# Core.net
KiCad netlist of a schematic drawn in Altium Designer
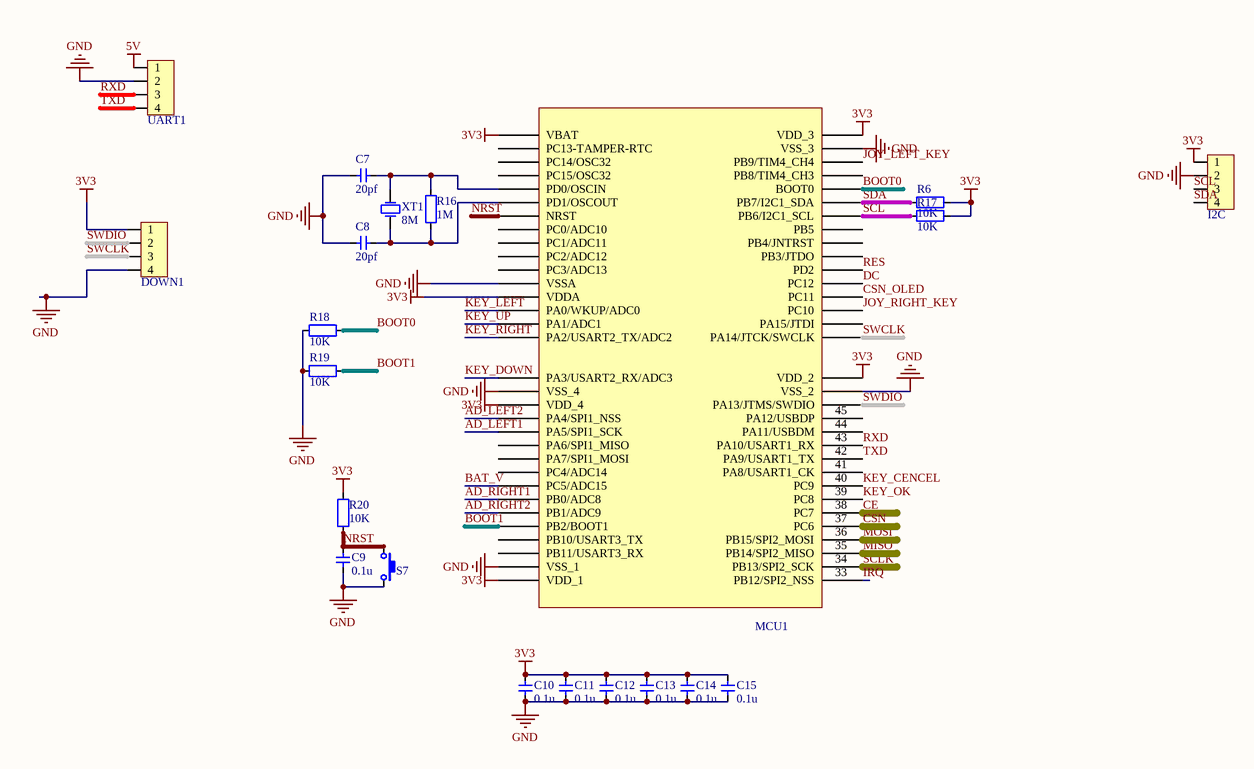
[diagram p0: Core.SchDoc]

(export (version "E")
  (design (tool "Eeschema 10.0.6"))
  (components
    (comp (ref "C7")
      (value "20pf")
      (footprint "PCB_PassiveCap:CAP_0603")
      (description "Capacitor")
      (fields (field (name "Comment") "Cap_0603"))
      (libsource (lib "SCH_Passive") (part "Cap_0603"))
    )
    (comp (ref "C8")
      (value "20pf")
      (footprint "PCB_PassiveCap:CAP_0603")
      (description "Capacitor")
      (fields (field (name "Comment") "Cap_0603"))
      (libsource (lib "SCH_Passive") (part "Cap_0603"))
    )
    (comp (ref "C9")
      (value "0.1u")
      (footprint "PCB_PassiveCap:CAP_0603")
      (description "Capacitor")
      (fields (field (name "Comment") "Cap_0603"))
      (libsource (lib "SCH_Passive") (part "Cap_0603"))
    )
    (comp (ref "C10")
      (value "0.1u")
      (footprint "PCB_PassiveCap:CAP_0603")
      (description "Capacitor")
      (fields (field (name "Comment") "Cap_0603"))
      (libsource (lib "SCH_Passive") (part "Cap_0603"))
    )
    (comp (ref "C11")
      (value "0.1u")
      (footprint "PCB_PassiveCap:CAP_0603")
      (description "Capacitor")
      (fields (field (name "Comment") "Cap_0603"))
      (libsource (lib "SCH_Passive") (part "Cap_0603"))
    )
    (comp (ref "C12")
      (value "0.1u")
      (footprint "PCB_PassiveCap:CAP_0603")
      (description "Capacitor")
      (fields (field (name "Comment") "Cap_0603"))
      (libsource (lib "SCH_Passive") (part "Cap_0603"))
    )
    (comp (ref "C13")
      (value "0.1u")
      (footprint "PCB_PassiveCap:CAP_0603")
      (description "Capacitor")
      (fields (field (name "Comment") "Cap_0603"))
      (libsource (lib "SCH_Passive") (part "Cap_0603"))
    )
    (comp (ref "C14")
      (value "0.1u")
      (footprint "PCB_PassiveCap:CAP_0603")
      (description "Capacitor")
      (fields (field (name "Comment") "Cap_0603"))
      (libsource (lib "SCH_Passive") (part "Cap_0603"))
    )
    (comp (ref "C15")
      (value "0.1u")
      (footprint "PCB_PassiveCap:CAP_0603")
      (description "Capacitor")
      (fields (field (name "Comment") "Cap_0603"))
      (libsource (lib "SCH_Passive") (part "Cap_0603"))
    )
    (comp (ref "DOWN1")
      (value "HDR1x4_2.54")
      (footprint "PCB_ConnectorHDR:HDR1x4_2.54_180")
      (description "Header")
      (libsource (lib "SCH_ConnectorHDR") (part "HDR1x4_2.54"))
    )
    (comp (ref "I2C")
      (value "HDR1x4_2.54")
      (footprint "PCB_ConnectorHDR:HDR1x4_2.54_180")
      (description "Header")
      (libsource (lib "SCH_ConnectorHDR") (part "HDR1x4_2.54"))
    )
    (comp (ref "MCU1")
      (value "STM32F103RC")
      (footprint "LQFP_P0.5_64")
      (description "MCU")
      (libsource (lib "SCH_IntegratedCircuit") (part "STM32F103RC"))
    )
    (comp (ref "R6")
      (value "10K")
      (footprint "PCB_PassiveRes:RES_0603")
      (description "Resistor")
      (fields (field (name "Comment") "Res_0603"))
      (libsource (lib "") (part "Res_0603_2"))
    )
    (comp (ref "R16")
      (value "1M")
      (footprint "PCB_PassiveRes:RES_0603")
      (description "Resistor")
      (fields (field (name "Comment") "Res_0603"))
      (libsource (lib "") (part "Res_0603_1"))
    )
    (comp (ref "R17")
      (value "10K")
      (footprint "PCB_PassiveRes:RES_0603")
      (description "Resistor")
      (fields (field (name "Comment") "Res_0603"))
      (libsource (lib "") (part "Res_0603_2"))
    )
    (comp (ref "R18")
      (value "10K")
      (footprint "PCB_PassiveRes:RES_0603")
      (description "Resistor")
      (fields (field (name "Comment") "Res_0603"))
      (libsource (lib "SCH_Passive") (part "Res_0603"))
    )
    (comp (ref "R19")
      (value "10K")
      (footprint "PCB_PassiveRes:RES_0603")
      (description "Resistor")
      (fields (field (name "Comment") "Res_0603"))
      (libsource (lib "SCH_Passive") (part "Res_0603"))
    )
    (comp (ref "R20")
      (value "10K")
      (footprint "PCB_PassiveRes:RES_0603")
      (description "Resistor")
      (fields (field (name "Comment") "Res_0603"))
      (libsource (lib "") (part "Res_0603_3"))
    )
    (comp (ref "S7")
      (value "ButtonTACT_3x4x2_180")
      (footprint "PCB_Switch:ButtonTACT_3x4x2_180H")
      (description "Button")
      (libsource (lib "SCH_Switch") (part "ButtonTACT_3x4x2_180"))
    )
    (comp (ref "UART1")
      (value "HDR1x4_2.54")
      (footprint "PCB_ConnectorHDR:HDR1x4_2.54_180")
      (description "Header")
      (libsource (lib "SCH_ConnectorHDR") (part "HDR1x4_2.54"))
    )
    (comp (ref "XT1")
      (value "8M")
      (footprint "PCB_Oscillator:XT_5032_2")
      (description "Crystal Oscillator")
      (fields (field (name "Comment") "XTAL_5032_2P"))
      (libsource (lib "SCH_Oscillator") (part "XTAL_5032_2P"))
    )
  )
  (nets
    (net (code "1") (name "/AD_LEFT1") (class "Default")
      (node (ref "MCU1") (pin "21") (pinfunction "PA5/SPI1_SCK_21") (pintype "passive"))
    )
    (net (code "2") (name "/AD_LEFT2") (class "Default")
      (node (ref "MCU1") (pin "20") (pinfunction "PA4/SPI1_NSS_20") (pintype "passive"))
    )
    (net (code "3") (name "/AD_RIGHT1") (class "Default")
      (node (ref "MCU1") (pin "26") (pinfunction "PB0/ADC8_26") (pintype "passive"))
    )
    (net (code "4") (name "/AD_RIGHT2") (class "Default")
      (node (ref "MCU1") (pin "27") (pinfunction "PB1/ADC9_27") (pintype "passive"))
    )
    (net (code "5") (name "/BAT_V") (class "Default")
      (node (ref "MCU1") (pin "25") (pinfunction "PC5/ADC15_25") (pintype "passive"))
    )
    (net (code "6") (name "/BOOT0") (class "Default")
      (node (ref "MCU1") (pin "60") (pinfunction "BOOT0_60") (pintype "passive"))
      (node (ref "R18") (pin "1") (pinfunction "1_1") (pintype "passive"))
    )
    (net (code "7") (name "/BOOT1") (class "Default")
      (node (ref "MCU1") (pin "28") (pinfunction "PB2/BOOT1_28") (pintype "passive"))
      (node (ref "R19") (pin "1") (pinfunction "1_1") (pintype "passive"))
    )
    (net (code "8") (name "/CE") (class "Default")
      (node (ref "MCU1") (pin "38") (pinfunction "PC7_38") (pintype "passive"))
    )
    (net (code "9") (name "/CSN") (class "Default")
      (node (ref "MCU1") (pin "37") (pinfunction "PC6_37") (pintype "passive"))
    )
    (net (code "10") (name "/CSN_OLED") (class "Default")
      (node (ref "MCU1") (pin "52") (pinfunction "PC11_52") (pintype "passive"))
    )
    (net (code "11") (name "/DC") (class "Default")
      (node (ref "MCU1") (pin "53") (pinfunction "PC12_53") (pintype "passive"))
    )
    (net (code "12") (name "/IRQ") (class "Default")
      (node (ref "MCU1") (pin "33") (pinfunction "PB12/SPI2_NSS_33") (pintype "passive"))
    )
    (net (code "13") (name "/JOY_LEFT_KEY") (class "Default")
      (node (ref "MCU1") (pin "62") (pinfunction "PB9/TIM4_CH4_62") (pintype "passive"))
    )
    (net (code "14") (name "/JOY_RIGHT_KEY") (class "Default")
      (node (ref "MCU1") (pin "51") (pinfunction "PC10_51") (pintype "passive"))
    )
    (net (code "15") (name "/KEY_CENCEL") (class "Default")
      (node (ref "MCU1") (pin "40") (pinfunction "PC9_40") (pintype "passive"))
    )
    (net (code "16") (name "/KEY_DOWN") (class "Default")
      (node (ref "MCU1") (pin "17") (pinfunction "PA3/USART2_RX/ADC3_17") (pintype "passive"))
    )
    (net (code "17") (name "/KEY_LEFT") (class "Default")
      (node (ref "MCU1") (pin "14") (pinfunction "PA0/WKUP/ADC0_14") (pintype "passive"))
    )
    (net (code "18") (name "/KEY_OK") (class "Default")
      (node (ref "MCU1") (pin "39") (pinfunction "PC8_39") (pintype "passive"))
    )
    (net (code "19") (name "/KEY_RIGHT") (class "Default")
      (node (ref "MCU1") (pin "16") (pinfunction "PA2/USART2_TX/ADC2_16") (pintype "passive"))
    )
    (net (code "20") (name "/KEY_UP") (class "Default")
      (node (ref "MCU1") (pin "15") (pinfunction "PA1/ADC1_15") (pintype "passive"))
    )
    (net (code "21") (name "/MISO") (class "Default")
      (node (ref "MCU1") (pin "35") (pinfunction "PB14/SPI2_MISO_35") (pintype "passive"))
    )
    (net (code "22") (name "/MOSI") (class "Default")
      (node (ref "MCU1") (pin "36") (pinfunction "PB15/SPI2_MOSI_36") (pintype "passive"))
    )
    (net (code "23") (name "/NRST") (class "Default")
      (node (ref "C9") (pin "2") (pinfunction "2_2") (pintype "passive"))
      (node (ref "MCU1") (pin "7") (pinfunction "NRST_7") (pintype "passive"))
      (node (ref "R20") (pin "2") (pinfunction "2_2") (pintype "passive"))
      (node (ref "S7") (pin "1") (pinfunction "1_1") (pintype "passive"))
    )
    (net (code "24") (name "/RES") (class "Default")
      (node (ref "MCU1") (pin "54") (pinfunction "PD2_54") (pintype "passive"))
    )
    (net (code "25") (name "/RXD") (class "Default")
      (node (ref "MCU1") (pin "43") (pinfunction "PA10/USART1_RX_43") (pintype "passive"))
      (node (ref "UART1") (pin "3") (pinfunction "3_3") (pintype "passive"))
    )
    (net (code "26") (name "/SCL") (class "Default")
      (node (ref "I2C") (pin "3") (pinfunction "3_3") (pintype "passive"))
      (node (ref "MCU1") (pin "58") (pinfunction "PB6/I2C1_SCL_58") (pintype "passive"))
      (node (ref "R17") (pin "1") (pinfunction "1_1") (pintype "passive"))
    )
    (net (code "27") (name "/SCLK") (class "Default")
      (node (ref "MCU1") (pin "34") (pinfunction "PB13/SPI2_SCK_34") (pintype "passive"))
    )
    (net (code "28") (name "/SDA") (class "Default")
      (node (ref "I2C") (pin "4") (pinfunction "4_4") (pintype "passive"))
      (node (ref "MCU1") (pin "59") (pinfunction "PB7/I2C1_SDA_59") (pintype "passive"))
      (node (ref "R6") (pin "1") (pinfunction "1_1") (pintype "passive"))
    )
    (net (code "29") (name "/SWCLK") (class "Default")
      (node (ref "DOWN1") (pin "3") (pinfunction "3_3") (pintype "passive"))
      (node (ref "MCU1") (pin "49") (pinfunction "PA14/JTCK/SWCLK_49") (pintype "passive"))
    )
    (net (code "30") (name "/SWDIO") (class "Default")
      (node (ref "DOWN1") (pin "2") (pinfunction "2_2") (pintype "passive"))
      (node (ref "MCU1") (pin "46") (pinfunction "PA13/JTMS/SWDIO_46") (pintype "passive"))
    )
    (net (code "31") (name "/TXD") (class "Default")
      (node (ref "MCU1") (pin "42") (pinfunction "PA9/USART1_TX_42") (pintype "passive"))
      (node (ref "UART1") (pin "4") (pinfunction "4_4") (pintype "passive"))
    )
    (net (code "32") (name "3V3") (class "Default")
      (node (ref "C10") (pin "2") (pinfunction "2_2") (pintype "passive"))
      (node (ref "C11") (pin "2") (pinfunction "2_2") (pintype "passive"))
      (node (ref "C12") (pin "2") (pinfunction "2_2") (pintype "passive"))
      (node (ref "C13") (pin "2") (pinfunction "2_2") (pintype "passive"))
      (node (ref "C14") (pin "2") (pinfunction "2_2") (pintype "passive"))
      (node (ref "C15") (pin "2") (pinfunction "2_2") (pintype "passive"))
      (node (ref "DOWN1") (pin "1") (pinfunction "1_1") (pintype "passive"))
      (node (ref "I2C") (pin "1") (pinfunction "1_1") (pintype "passive"))
      (node (ref "MCU1") (pin "1") (pinfunction "VBAT_1") (pintype "passive"))
      (node (ref "MCU1") (pin "13") (pinfunction "VDDA_13") (pintype "passive"))
      (node (ref "MCU1") (pin "19") (pinfunction "VDD_4_19") (pintype "passive"))
      (node (ref "MCU1") (pin "32") (pinfunction "VDD_1_32") (pintype "passive"))
      (node (ref "MCU1") (pin "48") (pinfunction "VDD_2_48") (pintype "passive"))
      (node (ref "MCU1") (pin "64") (pinfunction "VDD_3_64") (pintype "passive"))
      (node (ref "R17") (pin "2") (pinfunction "2_2") (pintype "passive"))
      (node (ref "R20") (pin "1") (pinfunction "1_1") (pintype "passive"))
      (node (ref "R6") (pin "2") (pinfunction "2_2") (pintype "passive"))
    )
    (net (code "33") (name "5V") (class "Default")
      (node (ref "UART1") (pin "1") (pinfunction "1_1") (pintype "passive"))
    )
    (net (code "34") (name "GND") (class "Default")
      (node (ref "C10") (pin "1") (pinfunction "1_1") (pintype "passive"))
      (node (ref "C11") (pin "1") (pinfunction "1_1") (pintype "passive"))
      (node (ref "C12") (pin "1") (pinfunction "1_1") (pintype "passive"))
      (node (ref "C13") (pin "1") (pinfunction "1_1") (pintype "passive"))
      (node (ref "C14") (pin "1") (pinfunction "1_1") (pintype "passive"))
      (node (ref "C15") (pin "1") (pinfunction "1_1") (pintype "passive"))
      (node (ref "C7") (pin "1") (pinfunction "1_1") (pintype "passive"))
      (node (ref "C8") (pin "1") (pinfunction "1_1") (pintype "passive"))
      (node (ref "C9") (pin "1") (pinfunction "1_1") (pintype "passive"))
      (node (ref "DOWN1") (pin "4") (pinfunction "4_4") (pintype "passive"))
      (node (ref "I2C") (pin "2") (pinfunction "2_2") (pintype "passive"))
      (node (ref "MCU1") (pin "12") (pinfunction "VSSA_12") (pintype "passive"))
      (node (ref "MCU1") (pin "18") (pinfunction "VSS_4_18") (pintype "passive"))
      (node (ref "MCU1") (pin "31") (pinfunction "VSS_1_31") (pintype "passive"))
      (node (ref "MCU1") (pin "47") (pinfunction "VSS_2_47") (pintype "passive"))
      (node (ref "MCU1") (pin "63") (pinfunction "VSS_3_63") (pintype "passive"))
      (node (ref "R18") (pin "2") (pinfunction "2_2") (pintype "passive"))
      (node (ref "R19") (pin "2") (pinfunction "2_2") (pintype "passive"))
      (node (ref "S7") (pin "2") (pinfunction "2_2") (pintype "passive"))
      (node (ref "UART1") (pin "2") (pinfunction "2_2") (pintype "passive"))
    )
    (net (code "35") (name "Net-(MCU1-PD0{slash}OSCIN)") (class "Default")
      (node (ref "C7") (pin "2") (pinfunction "2_2") (pintype "passive"))
      (node (ref "MCU1") (pin "5") (pinfunction "PD0/OSCIN_5") (pintype "passive"))
      (node (ref "R16") (pin "2") (pinfunction "2_2") (pintype "passive"))
      (node (ref "XT1") (pin "2") (pinfunction "OSC2_2") (pintype "passive"))
    )
    (net (code "36") (name "Net-(MCU1-PD1{slash}OSCOUT)") (class "Default")
      (node (ref "C8") (pin "2") (pinfunction "2_2") (pintype "passive"))
      (node (ref "MCU1") (pin "6") (pinfunction "PD1/OSCOUT_6") (pintype "passive"))
      (node (ref "R16") (pin "1") (pinfunction "1_1") (pintype "passive"))
      (node (ref "XT1") (pin "1") (pinfunction "OSC1_1") (pintype "passive"))
    )
    (net (code "37") (name "unconnected-(MCU1-PA6{slash}SPI1_MISO-Pad22)") (class "Default")
      (node (ref "MCU1") (pin "22") (pinfunction "PA6/SPI1_MISO_22") (pintype "passive"))
    )
    (net (code "38") (name "unconnected-(MCU1-PA7{slash}SPI1_MOSI-Pad23)") (class "Default")
      (node (ref "MCU1") (pin "23") (pinfunction "PA7/SPI1_MOSI_23") (pintype "passive"))
    )
    (net (code "39") (name "unconnected-(MCU1-PA8{slash}USART1_CK-Pad41)") (class "Default")
      (node (ref "MCU1") (pin "41") (pinfunction "PA8/USART1_CK_41") (pintype "passive"))
    )
    (net (code "40") (name "unconnected-(MCU1-PA11{slash}USBDM-Pad44)") (class "Default")
      (node (ref "MCU1") (pin "44") (pinfunction "PA11/USBDM_44") (pintype "passive"))
    )
    (net (code "41") (name "unconnected-(MCU1-PA12{slash}USBDP-Pad45)") (class "Default")
      (node (ref "MCU1") (pin "45") (pinfunction "PA12/USBDP_45") (pintype "passive"))
    )
    (net (code "42") (name "unconnected-(MCU1-PA15{slash}JTDI-Pad50)") (class "Default")
      (node (ref "MCU1") (pin "50") (pinfunction "PA15/JTDI_50") (pintype "passive"))
    )
    (net (code "43") (name "unconnected-(MCU1-PB3{slash}JTDO-Pad55)") (class "Default")
      (node (ref "MCU1") (pin "55") (pinfunction "PB3/JTDO_55") (pintype "passive"))
    )
    (net (code "44") (name "unconnected-(MCU1-PB4{slash}JNTRST-Pad56)") (class "Default")
      (node (ref "MCU1") (pin "56") (pinfunction "PB4/JNTRST_56") (pintype "passive"))
    )
    (net (code "45") (name "unconnected-(MCU1-PB5-Pad57)") (class "Default")
      (node (ref "MCU1") (pin "57") (pinfunction "PB5_57") (pintype "passive"))
    )
    (net (code "46") (name "unconnected-(MCU1-PB8{slash}TIM4_CH3-Pad61)") (class "Default")
      (node (ref "MCU1") (pin "61") (pinfunction "PB8/TIM4_CH3_61") (pintype "passive"))
    )
    (net (code "47") (name "unconnected-(MCU1-PB10{slash}USART3_TX-Pad29)") (class "Default")
      (node (ref "MCU1") (pin "29") (pinfunction "PB10/USART3_TX_29") (pintype "passive"))
    )
    (net (code "48") (name "unconnected-(MCU1-PB11{slash}USART3_RX-Pad30)") (class "Default")
      (node (ref "MCU1") (pin "30") (pinfunction "PB11/USART3_RX_30") (pintype "passive"))
    )
    (net (code "49") (name "unconnected-(MCU1-PC0{slash}ADC10-Pad8)") (class "Default")
      (node (ref "MCU1") (pin "8") (pinfunction "PC0/ADC10_8") (pintype "passive"))
    )
    (net (code "50") (name "unconnected-(MCU1-PC1{slash}ADC11-Pad9)") (class "Default")
      (node (ref "MCU1") (pin "9") (pinfunction "PC1/ADC11_9") (pintype "passive"))
    )
    (net (code "51") (name "unconnected-(MCU1-PC2{slash}ADC12-Pad10)") (class "Default")
      (node (ref "MCU1") (pin "10") (pinfunction "PC2/ADC12_10") (pintype "passive"))
    )
    (net (code "52") (name "unconnected-(MCU1-PC3{slash}ADC13-Pad11)") (class "Default")
      (node (ref "MCU1") (pin "11") (pinfunction "PC3/ADC13_11") (pintype "passive"))
    )
    (net (code "53") (name "unconnected-(MCU1-PC4{slash}ADC14-Pad24)") (class "Default")
      (node (ref "MCU1") (pin "24") (pinfunction "PC4/ADC14_24") (pintype "passive"))
    )
    (net (code "54") (name "unconnected-(MCU1-PC13-TAMPER-RTC-Pad2)") (class "Default")
      (node (ref "MCU1") (pin "2") (pinfunction "PC13-TAMPER-RTC_2") (pintype "passive"))
    )
    (net (code "55") (name "unconnected-(MCU1-PC14{slash}OSC32-Pad3)") (class "Default")
      (node (ref "MCU1") (pin "3") (pinfunction "PC14/OSC32_3") (pintype "passive"))
    )
    (net (code "56") (name "unconnected-(MCU1-PC15{slash}OSC32-Pad4)") (class "Default")
      (node (ref "MCU1") (pin "4") (pinfunction "PC15/OSC32_4") (pintype "passive"))
    )
  )
)
